# H03.net
KiCad netlist of a schematic drawn in EAGLE
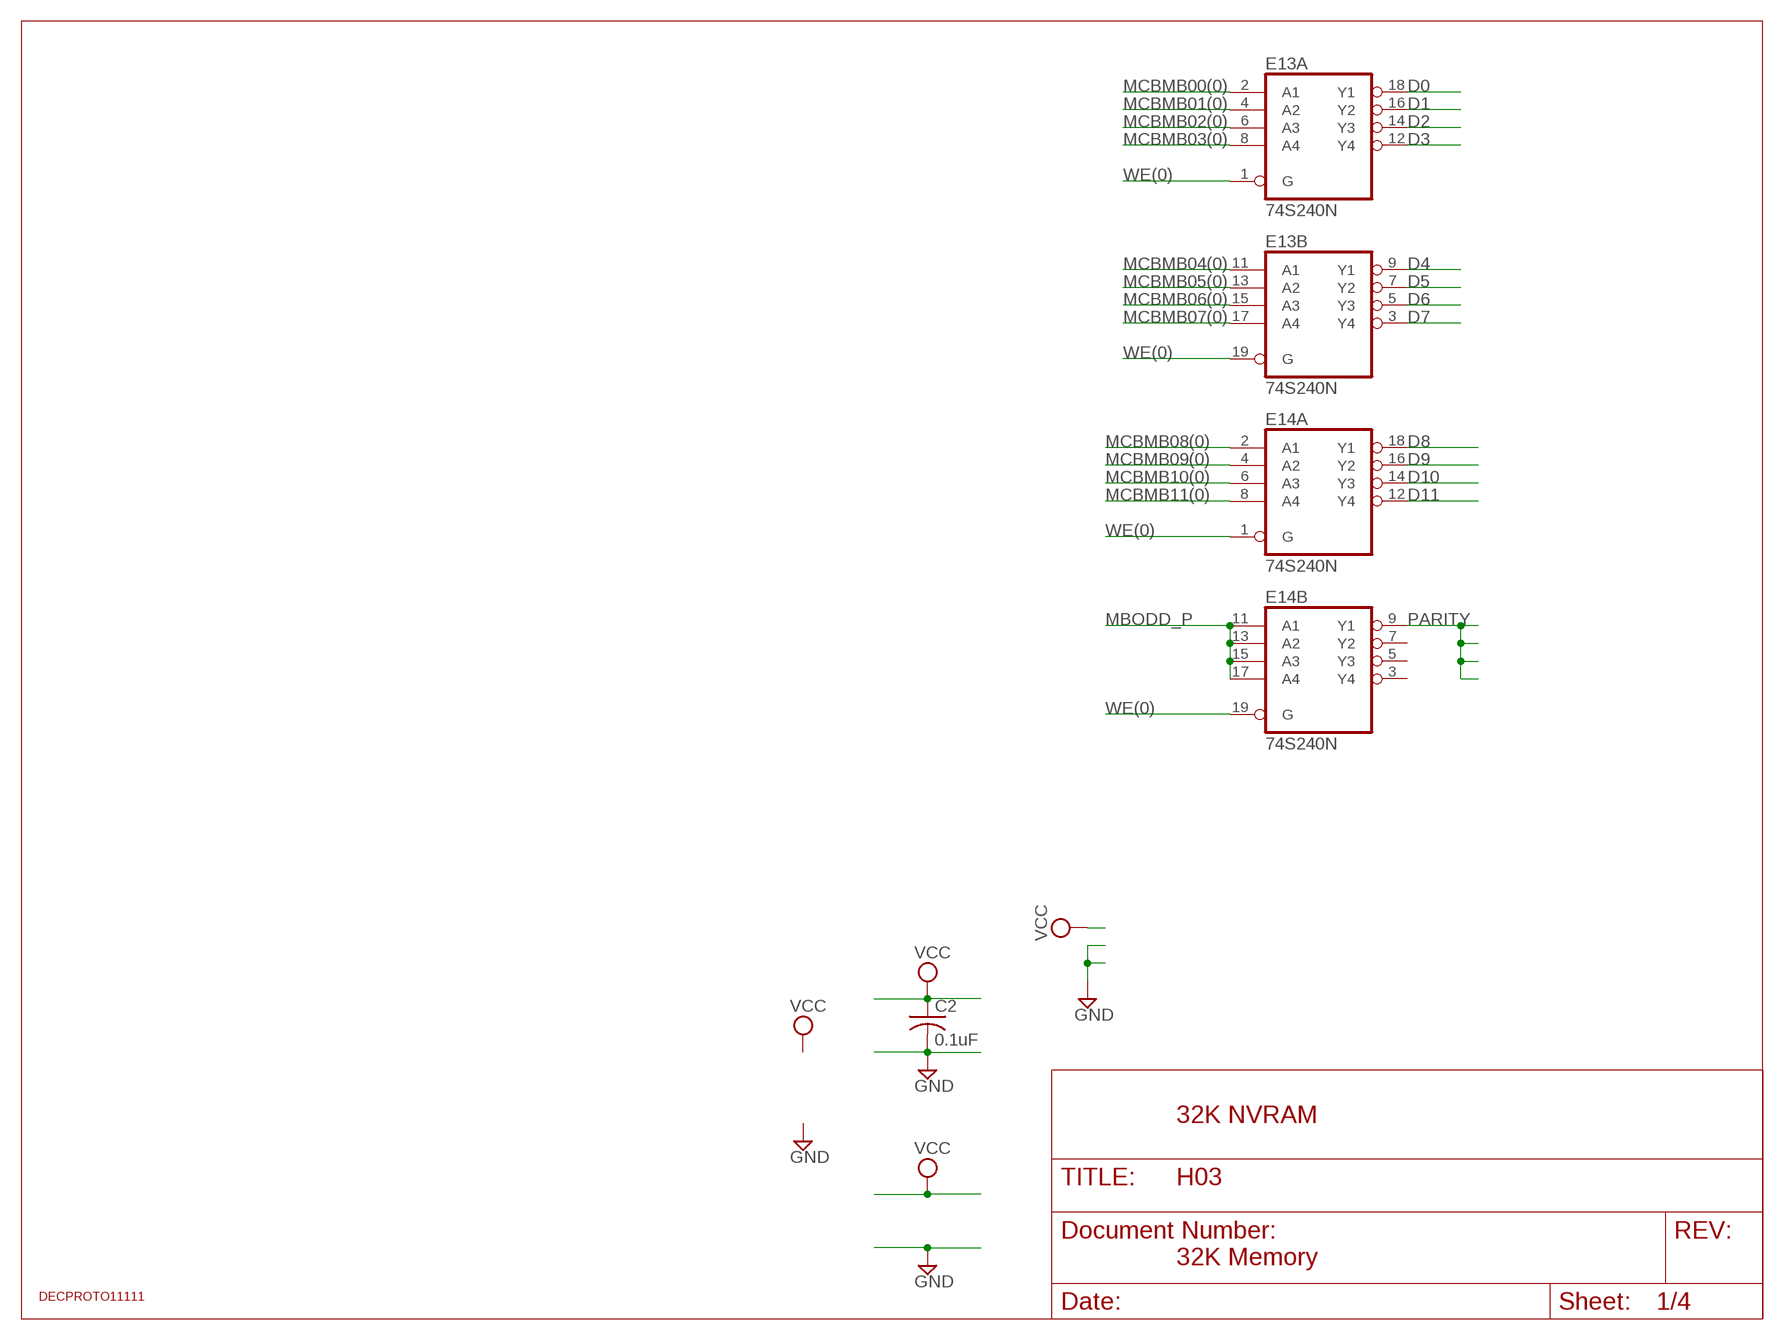
[diagram p0: schematic, sheet 1]
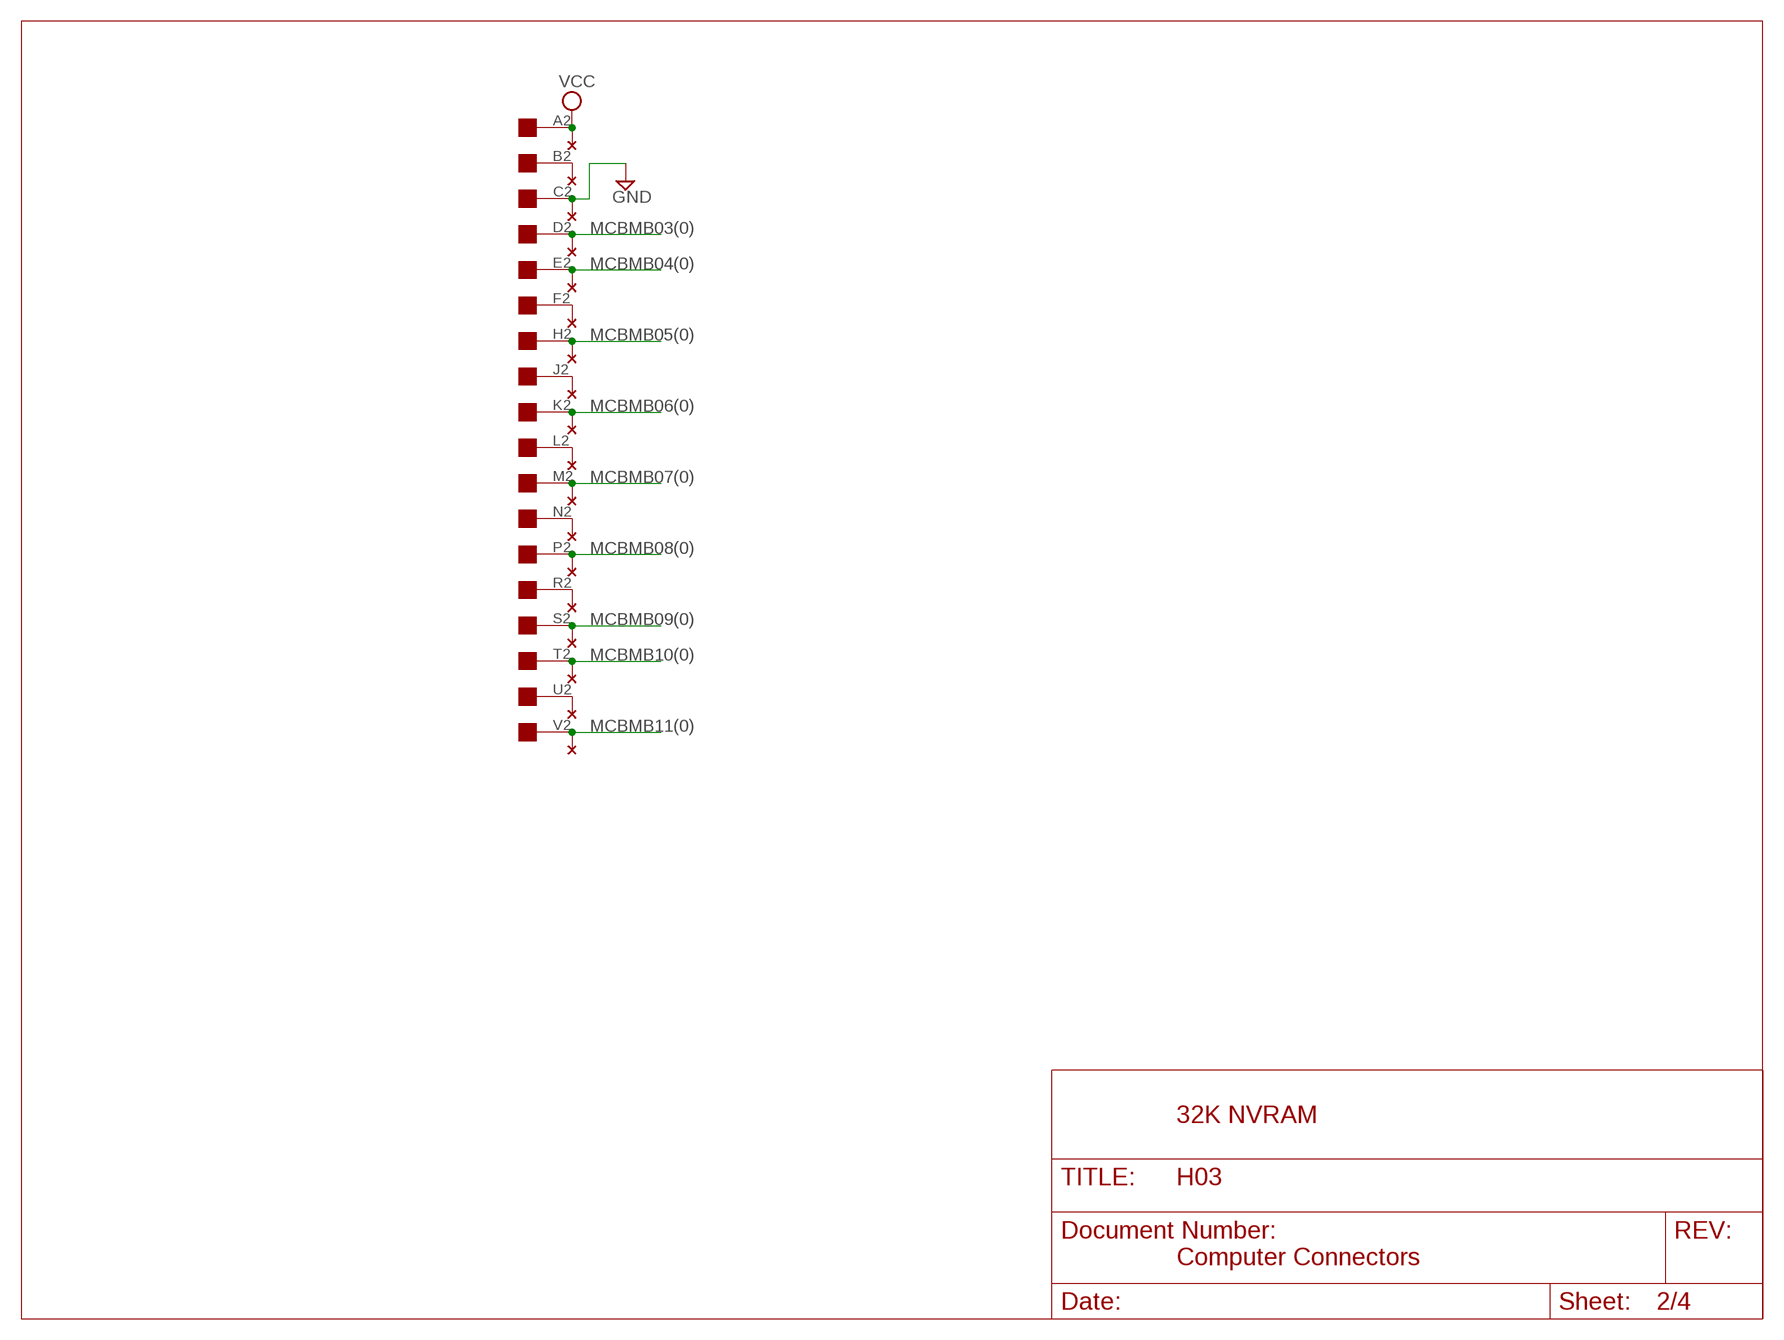
[diagram p1: schematic, sheet 2]
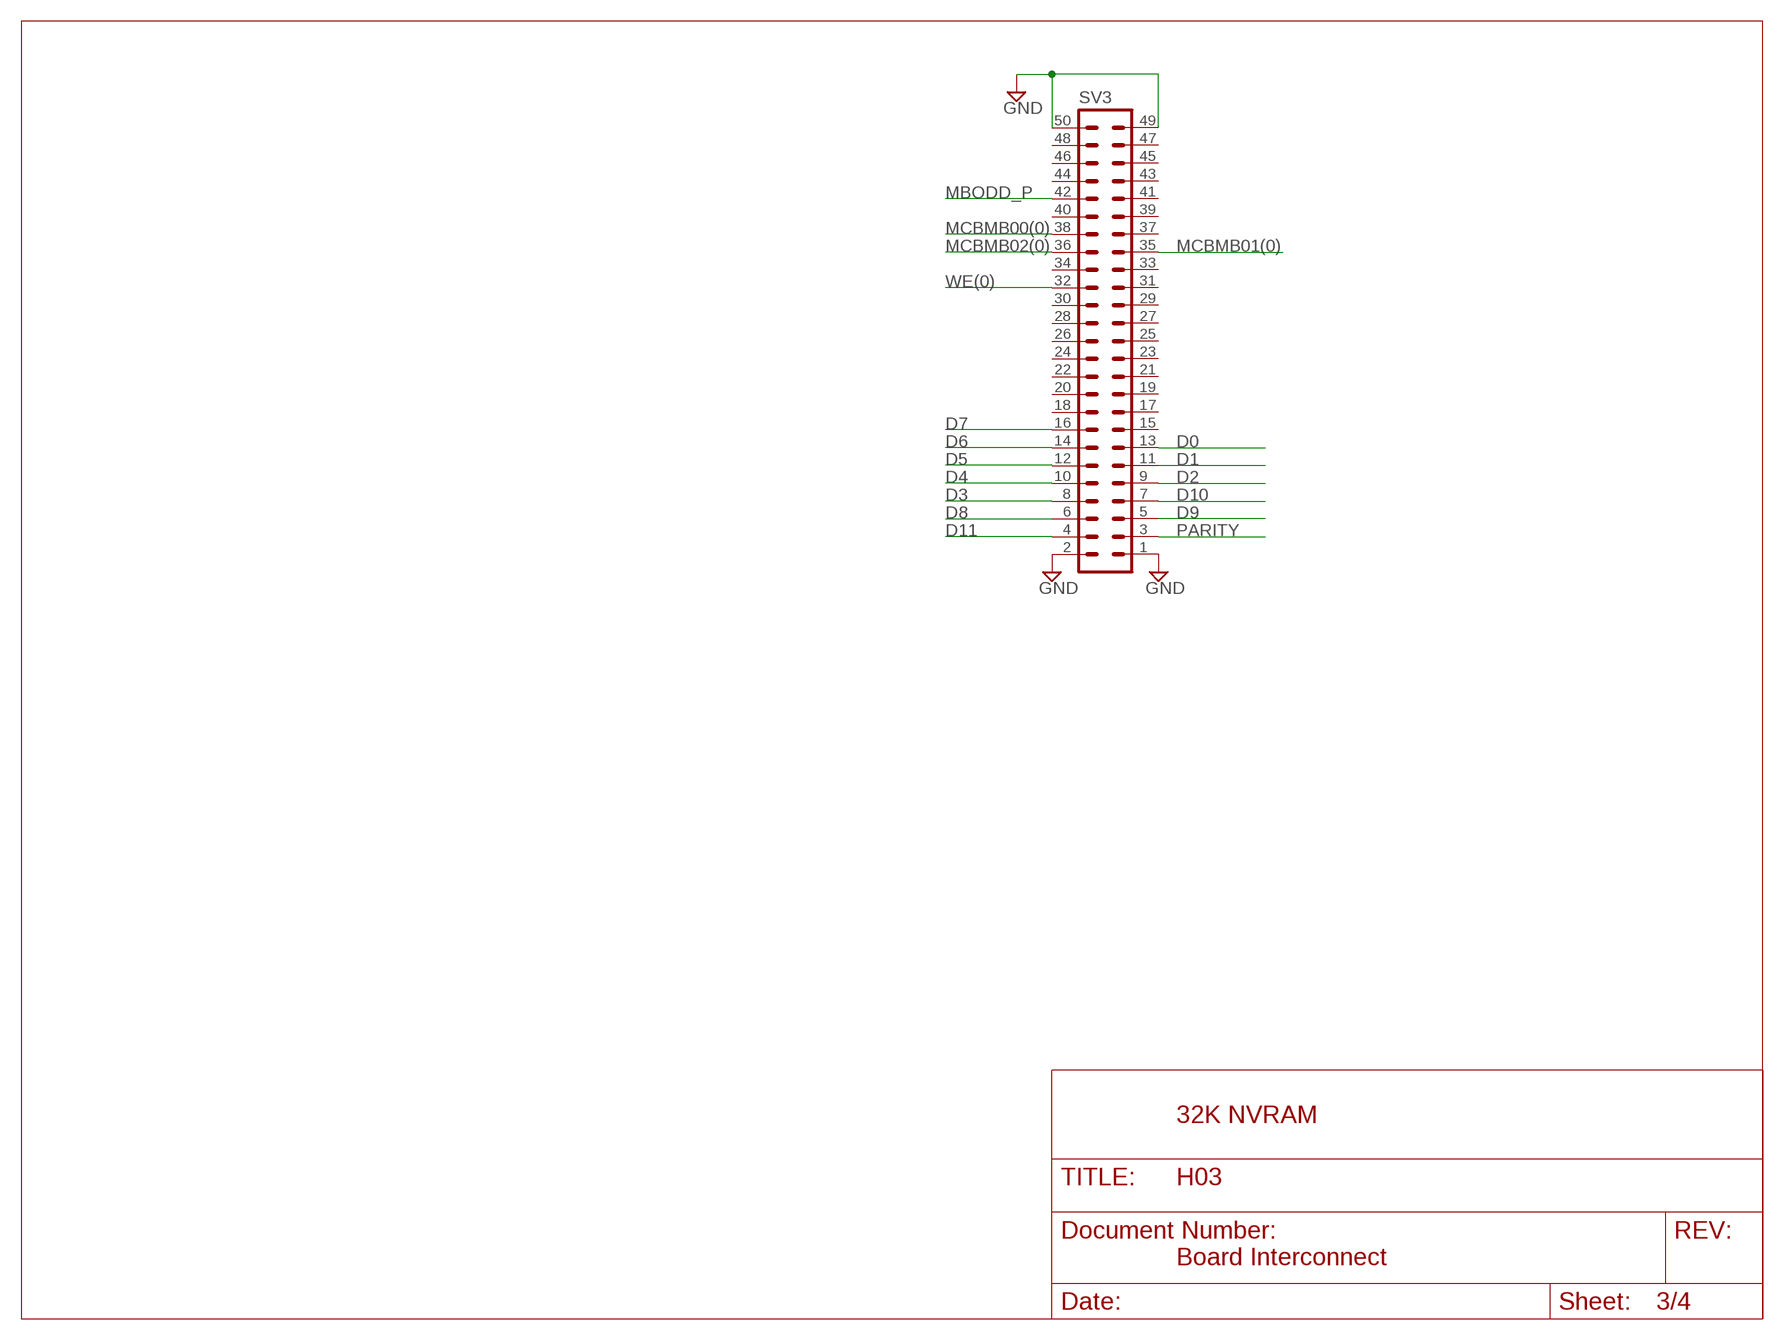
[diagram p2: schematic, sheet 3]
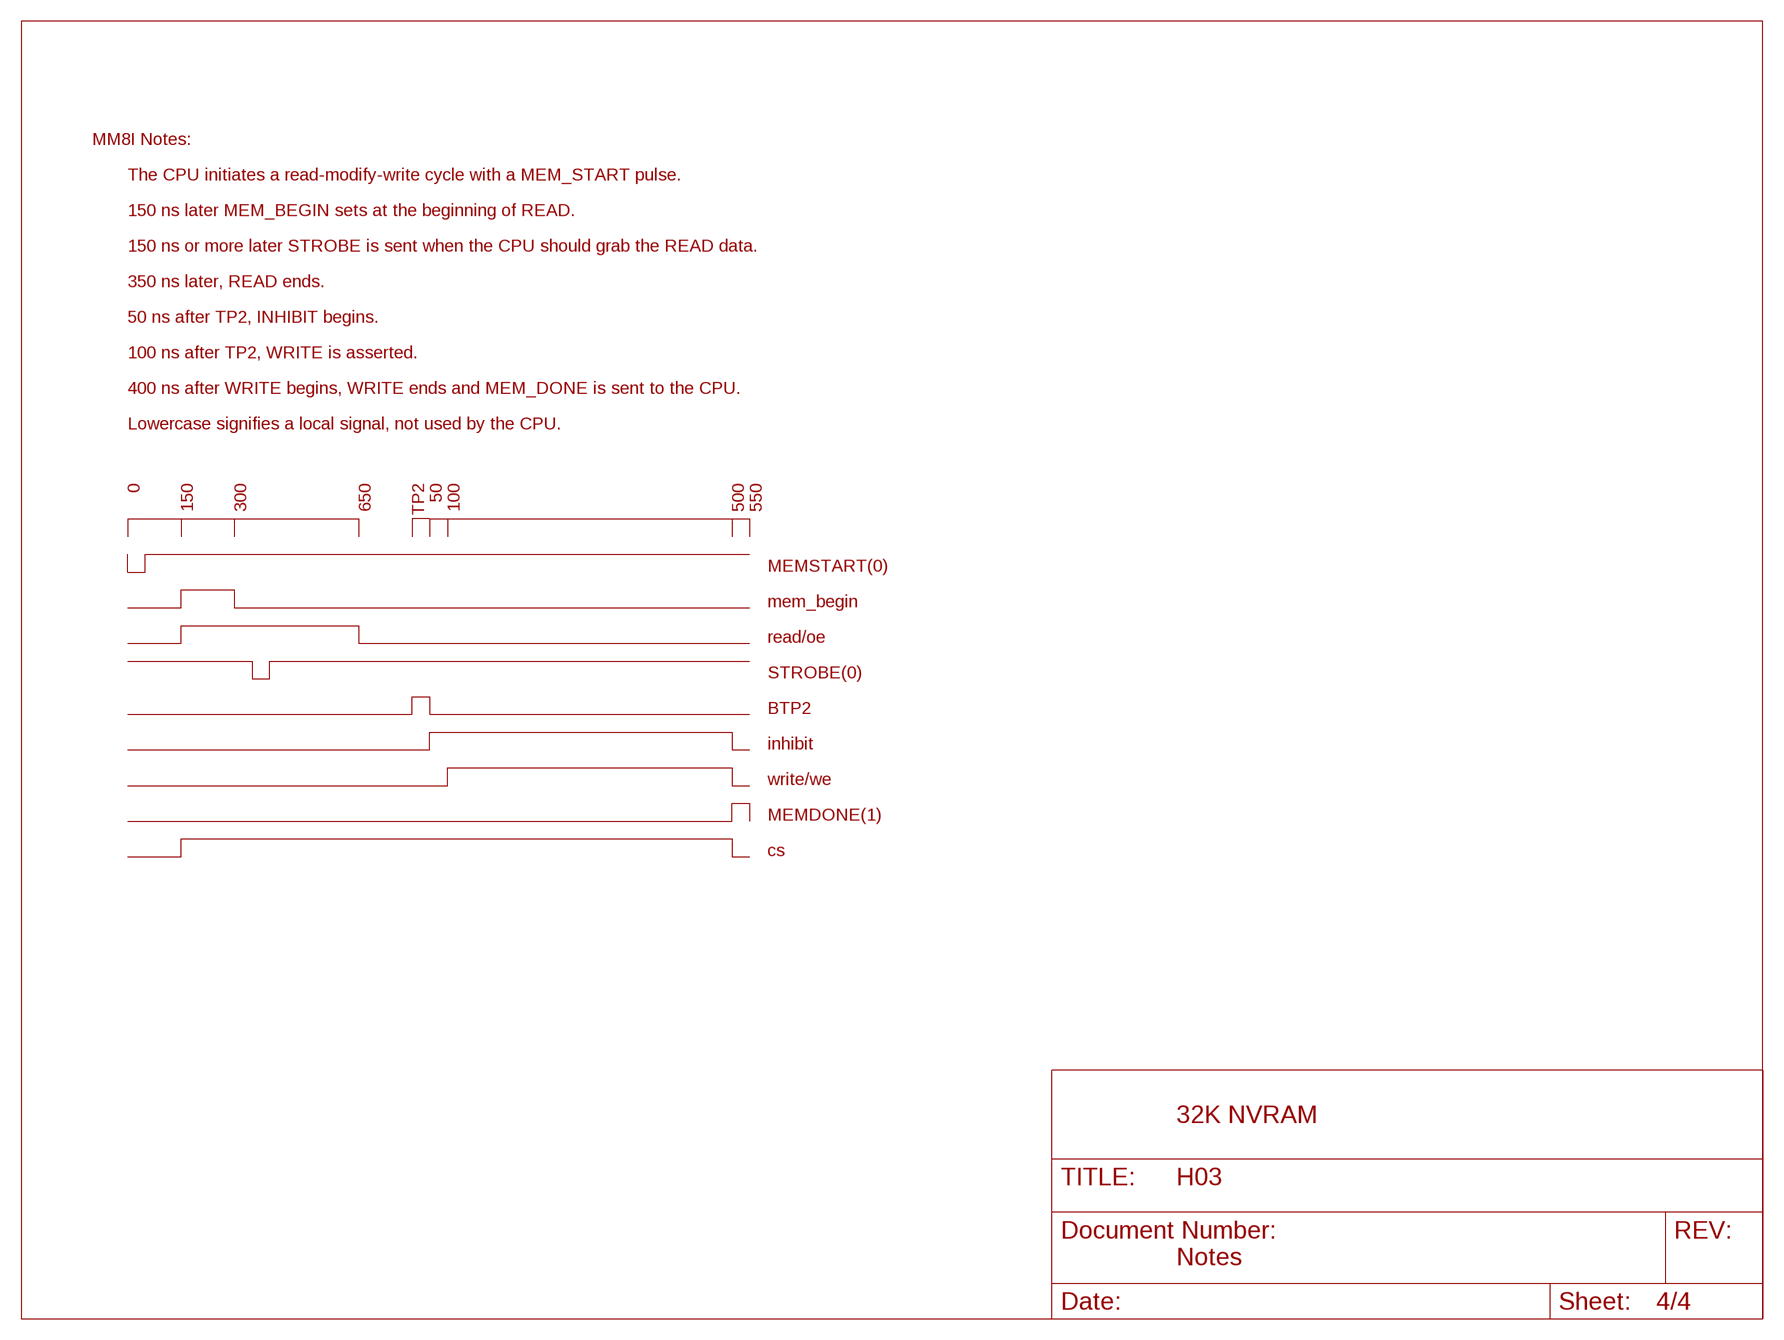
[diagram p3: schematic, sheet 4]

(export (version "E")
  (design (tool "Eeschema 10.0.6"))
  (components
    (comp (ref "H03")
      (value "EDGE-1")
      (footprint "eagle-import:EDGE-CON1")
      (libsource (lib "eagle-import") (part "EDGE-1"))
    )
    (comp (ref "U$3")
      (value "THRU-HOLE2")
      (footprint "eagle-import:THRU-HOLEB")
      (libsource (lib "eagle-import") (part "THRU-HOLE2"))
    )
    (comp (ref "C2")
      (value "0.1uF")
      (footprint "eagle-import:C050-025X075")
      (libsource (lib "eagle-import") (part "C-US050-025X075"))
    )
    (comp (ref "E13")
      (value "74S240N")
      (footprint "eagle-import:DIL20")
      (libsource (lib "eagle-import") (part "74240NS"))
    )
    (comp (ref "E14")
      (value "74S240N")
      (footprint "eagle-import:DIL20")
      (libsource (lib "eagle-import") (part "74240NS"))
    )
    (comp (ref "U$6")
      (value "DECPROTO11111")
      (footprint "eagle-import:DECPROTO11111")
      (libsource (lib "eagle-import") (part "DECPROTO11111"))
    )
    (comp (ref "SV3")
      (value "ML50L")
      (footprint "eagle-import:ML50L")
      (libsource (lib "eagle-import") (part "ML50L"))
    )
  )
  (nets
    (net (code "1") (name "D0") (class "Default")
      (node (ref "E13") (pin "18") (pinfunction "Y1_18") (pintype "tri_state"))
      (node (ref "SV3") (pin "13") (pinfunction "13_13") (pintype "passive"))
    )
    (net (code "2") (name "D1") (class "Default")
      (node (ref "E13") (pin "16") (pinfunction "Y2_16") (pintype "tri_state"))
      (node (ref "SV3") (pin "11") (pinfunction "11_11") (pintype "passive"))
    )
    (net (code "3") (name "D2") (class "Default")
      (node (ref "E13") (pin "14") (pinfunction "Y3_14") (pintype "tri_state"))
      (node (ref "SV3") (pin "9") (pinfunction "9_9") (pintype "passive"))
    )
    (net (code "4") (name "D3") (class "Default")
      (node (ref "E13") (pin "12") (pinfunction "Y4_12") (pintype "tri_state"))
      (node (ref "SV3") (pin "8") (pinfunction "8_8") (pintype "passive"))
    )
    (net (code "5") (name "D4") (class "Default")
      (node (ref "E13") (pin "9") (pinfunction "Y1_9") (pintype "tri_state"))
      (node (ref "SV3") (pin "10") (pinfunction "10_10") (pintype "passive"))
    )
    (net (code "6") (name "D5") (class "Default")
      (node (ref "E13") (pin "7") (pinfunction "Y2_7") (pintype "tri_state"))
      (node (ref "SV3") (pin "12") (pinfunction "12_12") (pintype "passive"))
    )
    (net (code "7") (name "D6") (class "Default")
      (node (ref "E13") (pin "5") (pinfunction "Y3_5") (pintype "tri_state"))
      (node (ref "SV3") (pin "14") (pinfunction "14_14") (pintype "passive"))
    )
    (net (code "8") (name "D7") (class "Default")
      (node (ref "E13") (pin "3") (pinfunction "Y4_3") (pintype "tri_state"))
      (node (ref "SV3") (pin "16") (pinfunction "16_16") (pintype "passive"))
    )
    (net (code "9") (name "D8") (class "Default")
      (node (ref "E14") (pin "18") (pinfunction "Y1_18") (pintype "tri_state"))
      (node (ref "SV3") (pin "6") (pinfunction "6_6") (pintype "passive"))
    )
    (net (code "10") (name "D9") (class "Default")
      (node (ref "E14") (pin "16") (pinfunction "Y2_16") (pintype "tri_state"))
      (node (ref "SV3") (pin "5") (pinfunction "5_5") (pintype "passive"))
    )
    (net (code "11") (name "D10") (class "Default")
      (node (ref "E14") (pin "14") (pinfunction "Y3_14") (pintype "tri_state"))
      (node (ref "SV3") (pin "7") (pinfunction "7_7") (pintype "passive"))
    )
    (net (code "12") (name "D11") (class "Default")
      (node (ref "E14") (pin "12") (pinfunction "Y4_12") (pintype "tri_state"))
      (node (ref "SV3") (pin "4") (pinfunction "4_4") (pintype "passive"))
    )
    (net (code "13") (name "GND") (class "Default")
      (node (ref "C2") (pin "2") (pinfunction "2_2") (pintype "passive"))
      (node (ref "H03") (pin "C2") (pinfunction "1_C2") (pintype "bidirectional"))
      (node (ref "SV3") (pin "1") (pinfunction "1_1") (pintype "passive"))
      (node (ref "SV3") (pin "2") (pinfunction "2_2") (pintype "passive"))
      (node (ref "SV3") (pin "49") (pinfunction "49_49") (pintype "passive"))
      (node (ref "SV3") (pin "50") (pinfunction "50_50") (pintype "passive"))
      (node (ref "U$3") (pin "C2") (pinfunction "P$1_C2") (pintype "passive"))
    )
    (net (code "14") (name "MBODD_P") (class "Default")
      (node (ref "E14") (pin "11") (pinfunction "A1_11") (pintype "input"))
      (node (ref "E14") (pin "13") (pinfunction "A2_13") (pintype "input"))
      (node (ref "E14") (pin "15") (pinfunction "A3_15") (pintype "input"))
      (node (ref "E14") (pin "17") (pinfunction "A4_17") (pintype "input"))
      (node (ref "SV3") (pin "42") (pinfunction "42_42") (pintype "passive"))
    )
    (net (code "15") (name "MCBMB00(0)") (class "Default")
      (node (ref "E13") (pin "2") (pinfunction "A1_2") (pintype "input"))
      (node (ref "SV3") (pin "38") (pinfunction "38_38") (pintype "passive"))
    )
    (net (code "16") (name "MCBMB01(0)") (class "Default")
      (node (ref "E13") (pin "4") (pinfunction "A2_4") (pintype "input"))
      (node (ref "SV3") (pin "35") (pinfunction "35_35") (pintype "passive"))
    )
    (net (code "17") (name "MCBMB02(0)") (class "Default")
      (node (ref "E13") (pin "6") (pinfunction "A3_6") (pintype "input"))
      (node (ref "SV3") (pin "36") (pinfunction "36_36") (pintype "passive"))
    )
    (net (code "18") (name "MCBMB03(0)") (class "Default")
      (node (ref "E13") (pin "8") (pinfunction "A4_8") (pintype "input"))
      (node (ref "H03") (pin "D2") (pinfunction "1_D2") (pintype "bidirectional"))
      (node (ref "U$3") (pin "D2") (pinfunction "P$1_D2") (pintype "passive"))
    )
    (net (code "19") (name "MCBMB04(0)") (class "Default")
      (node (ref "E13") (pin "11") (pinfunction "A1_11") (pintype "input"))
      (node (ref "H03") (pin "E2") (pinfunction "1_E2") (pintype "bidirectional"))
      (node (ref "U$3") (pin "E2") (pinfunction "P$1_E2") (pintype "passive"))
    )
    (net (code "20") (name "MCBMB05(0)") (class "Default")
      (node (ref "E13") (pin "13") (pinfunction "A2_13") (pintype "input"))
      (node (ref "H03") (pin "H2") (pinfunction "1_H2") (pintype "bidirectional"))
      (node (ref "U$3") (pin "H2") (pinfunction "P$1_H2") (pintype "passive"))
    )
    (net (code "21") (name "MCBMB06(0)") (class "Default")
      (node (ref "E13") (pin "15") (pinfunction "A3_15") (pintype "input"))
      (node (ref "H03") (pin "K2") (pinfunction "1_K2") (pintype "bidirectional"))
      (node (ref "U$3") (pin "K2") (pinfunction "P$1_K2") (pintype "passive"))
    )
    (net (code "22") (name "MCBMB07(0)") (class "Default")
      (node (ref "E13") (pin "17") (pinfunction "A4_17") (pintype "input"))
      (node (ref "H03") (pin "M2") (pinfunction "1_M2") (pintype "bidirectional"))
      (node (ref "U$3") (pin "M2") (pinfunction "P$1_M2") (pintype "passive"))
    )
    (net (code "23") (name "MCBMB08(0)") (class "Default")
      (node (ref "E14") (pin "2") (pinfunction "A1_2") (pintype "input"))
      (node (ref "H03") (pin "P2") (pinfunction "1_P2") (pintype "bidirectional"))
      (node (ref "U$3") (pin "P2") (pinfunction "P$1_P2") (pintype "passive"))
    )
    (net (code "24") (name "MCBMB09(0)") (class "Default")
      (node (ref "E14") (pin "4") (pinfunction "A2_4") (pintype "input"))
      (node (ref "H03") (pin "S2") (pinfunction "1_S2") (pintype "bidirectional"))
      (node (ref "U$3") (pin "S2") (pinfunction "P$1_S2") (pintype "passive"))
    )
    (net (code "25") (name "MCBMB10(0)") (class "Default")
      (node (ref "E14") (pin "6") (pinfunction "A3_6") (pintype "input"))
      (node (ref "H03") (pin "T2") (pinfunction "1_T2") (pintype "bidirectional"))
      (node (ref "U$3") (pin "T2") (pinfunction "P$1_T2") (pintype "passive"))
    )
    (net (code "26") (name "MCBMB11(0)") (class "Default")
      (node (ref "E14") (pin "8") (pinfunction "A4_8") (pintype "input"))
      (node (ref "H03") (pin "V2") (pinfunction "1_V2") (pintype "bidirectional"))
      (node (ref "U$3") (pin "V2") (pinfunction "P$1_V2") (pintype "passive"))
    )
    (net (code "27") (name "Net-(H03B-1)") (class "Default")
      (node (ref "H03") (pin "B2") (pinfunction "1_B2") (pintype "bidirectional"))
      (node (ref "U$3") (pin "B2") (pinfunction "P$1_B2") (pintype "passive"))
    )
    (net (code "28") (name "Net-(H03F-1)") (class "Default")
      (node (ref "H03") (pin "F2") (pinfunction "1_F2") (pintype "bidirectional"))
      (node (ref "U$3") (pin "F2") (pinfunction "P$1_F2") (pintype "passive"))
    )
    (net (code "29") (name "Net-(H03H-1)") (class "Default")
      (node (ref "H03") (pin "J2") (pinfunction "1_J2") (pintype "bidirectional"))
      (node (ref "U$3") (pin "J2") (pinfunction "P$1_J2") (pintype "passive"))
    )
    (net (code "30") (name "Net-(H03J-1)") (class "Default")
      (node (ref "H03") (pin "L2") (pinfunction "1_L2") (pintype "bidirectional"))
      (node (ref "U$3") (pin "L2") (pinfunction "P$1_L2") (pintype "passive"))
    )
    (net (code "31") (name "Net-(H03L-1)") (class "Default")
      (node (ref "H03") (pin "N2") (pinfunction "1_N2") (pintype "bidirectional"))
      (node (ref "U$3") (pin "N2") (pinfunction "P$1_N2") (pintype "passive"))
    )
    (net (code "32") (name "Net-(H03N-1)") (class "Default")
      (node (ref "H03") (pin "R2") (pinfunction "1_R2") (pintype "bidirectional"))
      (node (ref "U$3") (pin "R2") (pinfunction "P$1_R2") (pintype "passive"))
    )
    (net (code "33") (name "Net-(H03Q-1)") (class "Default")
      (node (ref "H03") (pin "U2") (pinfunction "1_U2") (pintype "bidirectional"))
      (node (ref "U$3") (pin "U2") (pinfunction "P$1_U2") (pintype "passive"))
    )
    (net (code "34") (name "PARITY") (class "Default")
      (node (ref "E14") (pin "9") (pinfunction "Y1_9") (pintype "tri_state"))
      (node (ref "SV3") (pin "3") (pinfunction "3_3") (pintype "passive"))
    )
    (net (code "35") (name "VCC") (class "Default")
      (node (ref "C2") (pin "1") (pinfunction "1_1") (pintype "passive"))
      (node (ref "H03") (pin "A2") (pinfunction "1_A2") (pintype "bidirectional"))
      (node (ref "U$3") (pin "A2") (pinfunction "P$1_A2") (pintype "passive"))
    )
    (net (code "36") (name "WE(0)") (class "Default")
      (node (ref "E13") (pin "1") (pinfunction "G_1") (pintype "input"))
      (node (ref "E13") (pin "19") (pinfunction "G_19") (pintype "input"))
      (node (ref "E14") (pin "1") (pinfunction "G_1") (pintype "input"))
      (node (ref "E14") (pin "19") (pinfunction "G_19") (pintype "input"))
      (node (ref "SV3") (pin "32") (pinfunction "32_32") (pintype "passive"))
    )
    (net (code "37") (name "unconnected-(E14B-Y2-Pad7)") (class "Default")
      (node (ref "E14") (pin "7") (pinfunction "Y2_7") (pintype "tri_state"))
    )
    (net (code "38") (name "unconnected-(E14B-Y3-Pad5)") (class "Default")
      (node (ref "E14") (pin "5") (pinfunction "Y3_5") (pintype "tri_state"))
    )
    (net (code "39") (name "unconnected-(E14B-Y4-Pad3)") (class "Default")
      (node (ref "E14") (pin "3") (pinfunction "Y4_3") (pintype "tri_state"))
    )
    (net (code "40") (name "unconnected-(SV3-Pad15)") (class "Default")
      (node (ref "SV3") (pin "15") (pinfunction "15_15") (pintype "passive"))
    )
    (net (code "41") (name "unconnected-(SV3-Pad17)") (class "Default")
      (node (ref "SV3") (pin "17") (pinfunction "17_17") (pintype "passive"))
    )
    (net (code "42") (name "unconnected-(SV3-Pad18)") (class "Default")
      (node (ref "SV3") (pin "18") (pinfunction "18_18") (pintype "passive"))
    )
    (net (code "43") (name "unconnected-(SV3-Pad19)") (class "Default")
      (node (ref "SV3") (pin "19") (pinfunction "19_19") (pintype "passive"))
    )
    (net (code "44") (name "unconnected-(SV3-Pad20)") (class "Default")
      (node (ref "SV3") (pin "20") (pinfunction "20_20") (pintype "passive"))
    )
    (net (code "45") (name "unconnected-(SV3-Pad21)") (class "Default")
      (node (ref "SV3") (pin "21") (pinfunction "21_21") (pintype "passive"))
    )
    (net (code "46") (name "unconnected-(SV3-Pad22)") (class "Default")
      (node (ref "SV3") (pin "22") (pinfunction "22_22") (pintype "passive"))
    )
    (net (code "47") (name "unconnected-(SV3-Pad23)") (class "Default")
      (node (ref "SV3") (pin "23") (pinfunction "23_23") (pintype "passive"))
    )
    (net (code "48") (name "unconnected-(SV3-Pad24)") (class "Default")
      (node (ref "SV3") (pin "24") (pinfunction "24_24") (pintype "passive"))
    )
    (net (code "49") (name "unconnected-(SV3-Pad25)") (class "Default")
      (node (ref "SV3") (pin "25") (pinfunction "25_25") (pintype "passive"))
    )
    (net (code "50") (name "unconnected-(SV3-Pad26)") (class "Default")
      (node (ref "SV3") (pin "26") (pinfunction "26_26") (pintype "passive"))
    )
    (net (code "51") (name "unconnected-(SV3-Pad27)") (class "Default")
      (node (ref "SV3") (pin "27") (pinfunction "27_27") (pintype "passive"))
    )
    (net (code "52") (name "unconnected-(SV3-Pad28)") (class "Default")
      (node (ref "SV3") (pin "28") (pinfunction "28_28") (pintype "passive"))
    )
    (net (code "53") (name "unconnected-(SV3-Pad29)") (class "Default")
      (node (ref "SV3") (pin "29") (pinfunction "29_29") (pintype "passive"))
    )
    (net (code "54") (name "unconnected-(SV3-Pad30)") (class "Default")
      (node (ref "SV3") (pin "30") (pinfunction "30_30") (pintype "passive"))
    )
    (net (code "55") (name "unconnected-(SV3-Pad31)") (class "Default")
      (node (ref "SV3") (pin "31") (pinfunction "31_31") (pintype "passive"))
    )
    (net (code "56") (name "unconnected-(SV3-Pad33)") (class "Default")
      (node (ref "SV3") (pin "33") (pinfunction "33_33") (pintype "passive"))
    )
    (net (code "57") (name "unconnected-(SV3-Pad34)") (class "Default")
      (node (ref "SV3") (pin "34") (pinfunction "34_34") (pintype "passive"))
    )
    (net (code "58") (name "unconnected-(SV3-Pad37)") (class "Default")
      (node (ref "SV3") (pin "37") (pinfunction "37_37") (pintype "passive"))
    )
    (net (code "59") (name "unconnected-(SV3-Pad39)") (class "Default")
      (node (ref "SV3") (pin "39") (pinfunction "39_39") (pintype "passive"))
    )
    (net (code "60") (name "unconnected-(SV3-Pad40)") (class "Default")
      (node (ref "SV3") (pin "40") (pinfunction "40_40") (pintype "passive"))
    )
    (net (code "61") (name "unconnected-(SV3-Pad41)") (class "Default")
      (node (ref "SV3") (pin "41") (pinfunction "41_41") (pintype "passive"))
    )
    (net (code "62") (name "unconnected-(SV3-Pad43)") (class "Default")
      (node (ref "SV3") (pin "43") (pinfunction "43_43") (pintype "passive"))
    )
    (net (code "63") (name "unconnected-(SV3-Pad44)") (class "Default")
      (node (ref "SV3") (pin "44") (pinfunction "44_44") (pintype "passive"))
    )
    (net (code "64") (name "unconnected-(SV3-Pad45)") (class "Default")
      (node (ref "SV3") (pin "45") (pinfunction "45_45") (pintype "passive"))
    )
    (net (code "65") (name "unconnected-(SV3-Pad46)") (class "Default")
      (node (ref "SV3") (pin "46") (pinfunction "46_46") (pintype "passive"))
    )
    (net (code "66") (name "unconnected-(SV3-Pad47)") (class "Default")
      (node (ref "SV3") (pin "47") (pinfunction "47_47") (pintype "passive"))
    )
    (net (code "67") (name "unconnected-(SV3-Pad48)") (class "Default")
      (node (ref "SV3") (pin "48") (pinfunction "48_48") (pintype "passive"))
    )
  )
)
